# MotorConnection.net
KiCad netlist of a schematic drawn in EAGLE
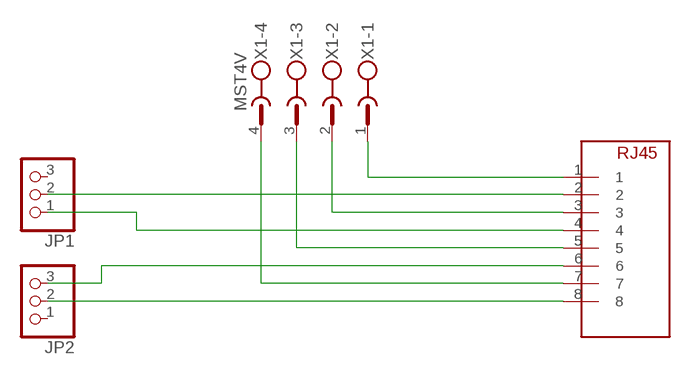
[diagram p0: schematic, sheet 1]

(export (version "E")
  (design (tool "Eeschema 10.0.6"))
  (components
    (comp (ref "JP1")
      (value "PINHD-1X3")
      (footprint "eagle-import:1X03")
      (libsource (lib "eagle-import") (part "PINHD-1X3"))
    )
    (comp (ref "JP2")
      (value "PINHD-1X3")
      (footprint "eagle-import:1X03")
      (libsource (lib "eagle-import") (part "PINHD-1X3"))
    )
    (comp (ref "WEIDMUELLER_RJ1")
      (value "WEIDMUELLER_RJ45")
      (footprint "eagle-import:WEIDMUELLER_RJ45")
      (libsource (lib "eagle-import") (part "WEIDMUELLER_RJ45"))
    )
    (comp (ref "X1")
      (value "MST4V")
      (footprint "eagle-import:MSTBV4")
      (libsource (lib "eagle-import") (part "MST4V"))
    )
  )
  (nets
    (net (code "1") (name "Net-(JP1-Pad1)") (class "Default")
      (node (ref "JP1") (pin "1") (pinfunction "1_1") (pintype "passive"))
      (node (ref "WEIDMUELLER_RJ1") (pin "4") (pinfunction "4_4") (pintype "bidirectional"))
    )
    (net (code "2") (name "Net-(JP1-Pad2)") (class "Default")
      (node (ref "JP1") (pin "2") (pinfunction "2_2") (pintype "passive"))
      (node (ref "WEIDMUELLER_RJ1") (pin "2") (pinfunction "2_2") (pintype "bidirectional"))
    )
    (net (code "3") (name "Net-(JP2-Pad2)") (class "Default")
      (node (ref "JP2") (pin "2") (pinfunction "2_2") (pintype "passive"))
      (node (ref "WEIDMUELLER_RJ1") (pin "8") (pinfunction "8_8") (pintype "bidirectional"))
    )
    (net (code "4") (name "Net-(JP2-Pad3)") (class "Default")
      (node (ref "JP2") (pin "3") (pinfunction "3_3") (pintype "passive"))
      (node (ref "WEIDMUELLER_RJ1") (pin "6") (pinfunction "6_6") (pintype "bidirectional"))
    )
    (net (code "5") (name "Net-(WEIDMUELLER_RJ1-Pad1)") (class "Default")
      (node (ref "WEIDMUELLER_RJ1") (pin "1") (pinfunction "1_1") (pintype "bidirectional"))
      (node (ref "X1") (pin "1") (pinfunction "1_1") (pintype "passive"))
    )
    (net (code "6") (name "Net-(X1B-1)") (class "Default")
      (node (ref "WEIDMUELLER_RJ1") (pin "3") (pinfunction "3_3") (pintype "bidirectional"))
      (node (ref "X1") (pin "2") (pinfunction "1_2") (pintype "passive"))
    )
    (net (code "7") (name "Net-(X1C-1)") (class "Default")
      (node (ref "WEIDMUELLER_RJ1") (pin "5") (pinfunction "5_5") (pintype "bidirectional"))
      (node (ref "X1") (pin "3") (pinfunction "1_3") (pintype "passive"))
    )
    (net (code "8") (name "Net-(X1D-1)") (class "Default")
      (node (ref "WEIDMUELLER_RJ1") (pin "7") (pinfunction "7_7") (pintype "bidirectional"))
      (node (ref "X1") (pin "4") (pinfunction "1_4") (pintype "passive"))
    )
    (net (code "9") (name "unconnected-(JP1-Pad3)") (class "Default")
      (node (ref "JP1") (pin "3") (pinfunction "3_3") (pintype "passive"))
    )
    (net (code "10") (name "unconnected-(JP2-Pad1)") (class "Default")
      (node (ref "JP2") (pin "1") (pinfunction "1_1") (pintype "passive"))
    )
  )
)
